# MotherBoard.net
KiCad netlist of a schematic drawn in Altium Designer
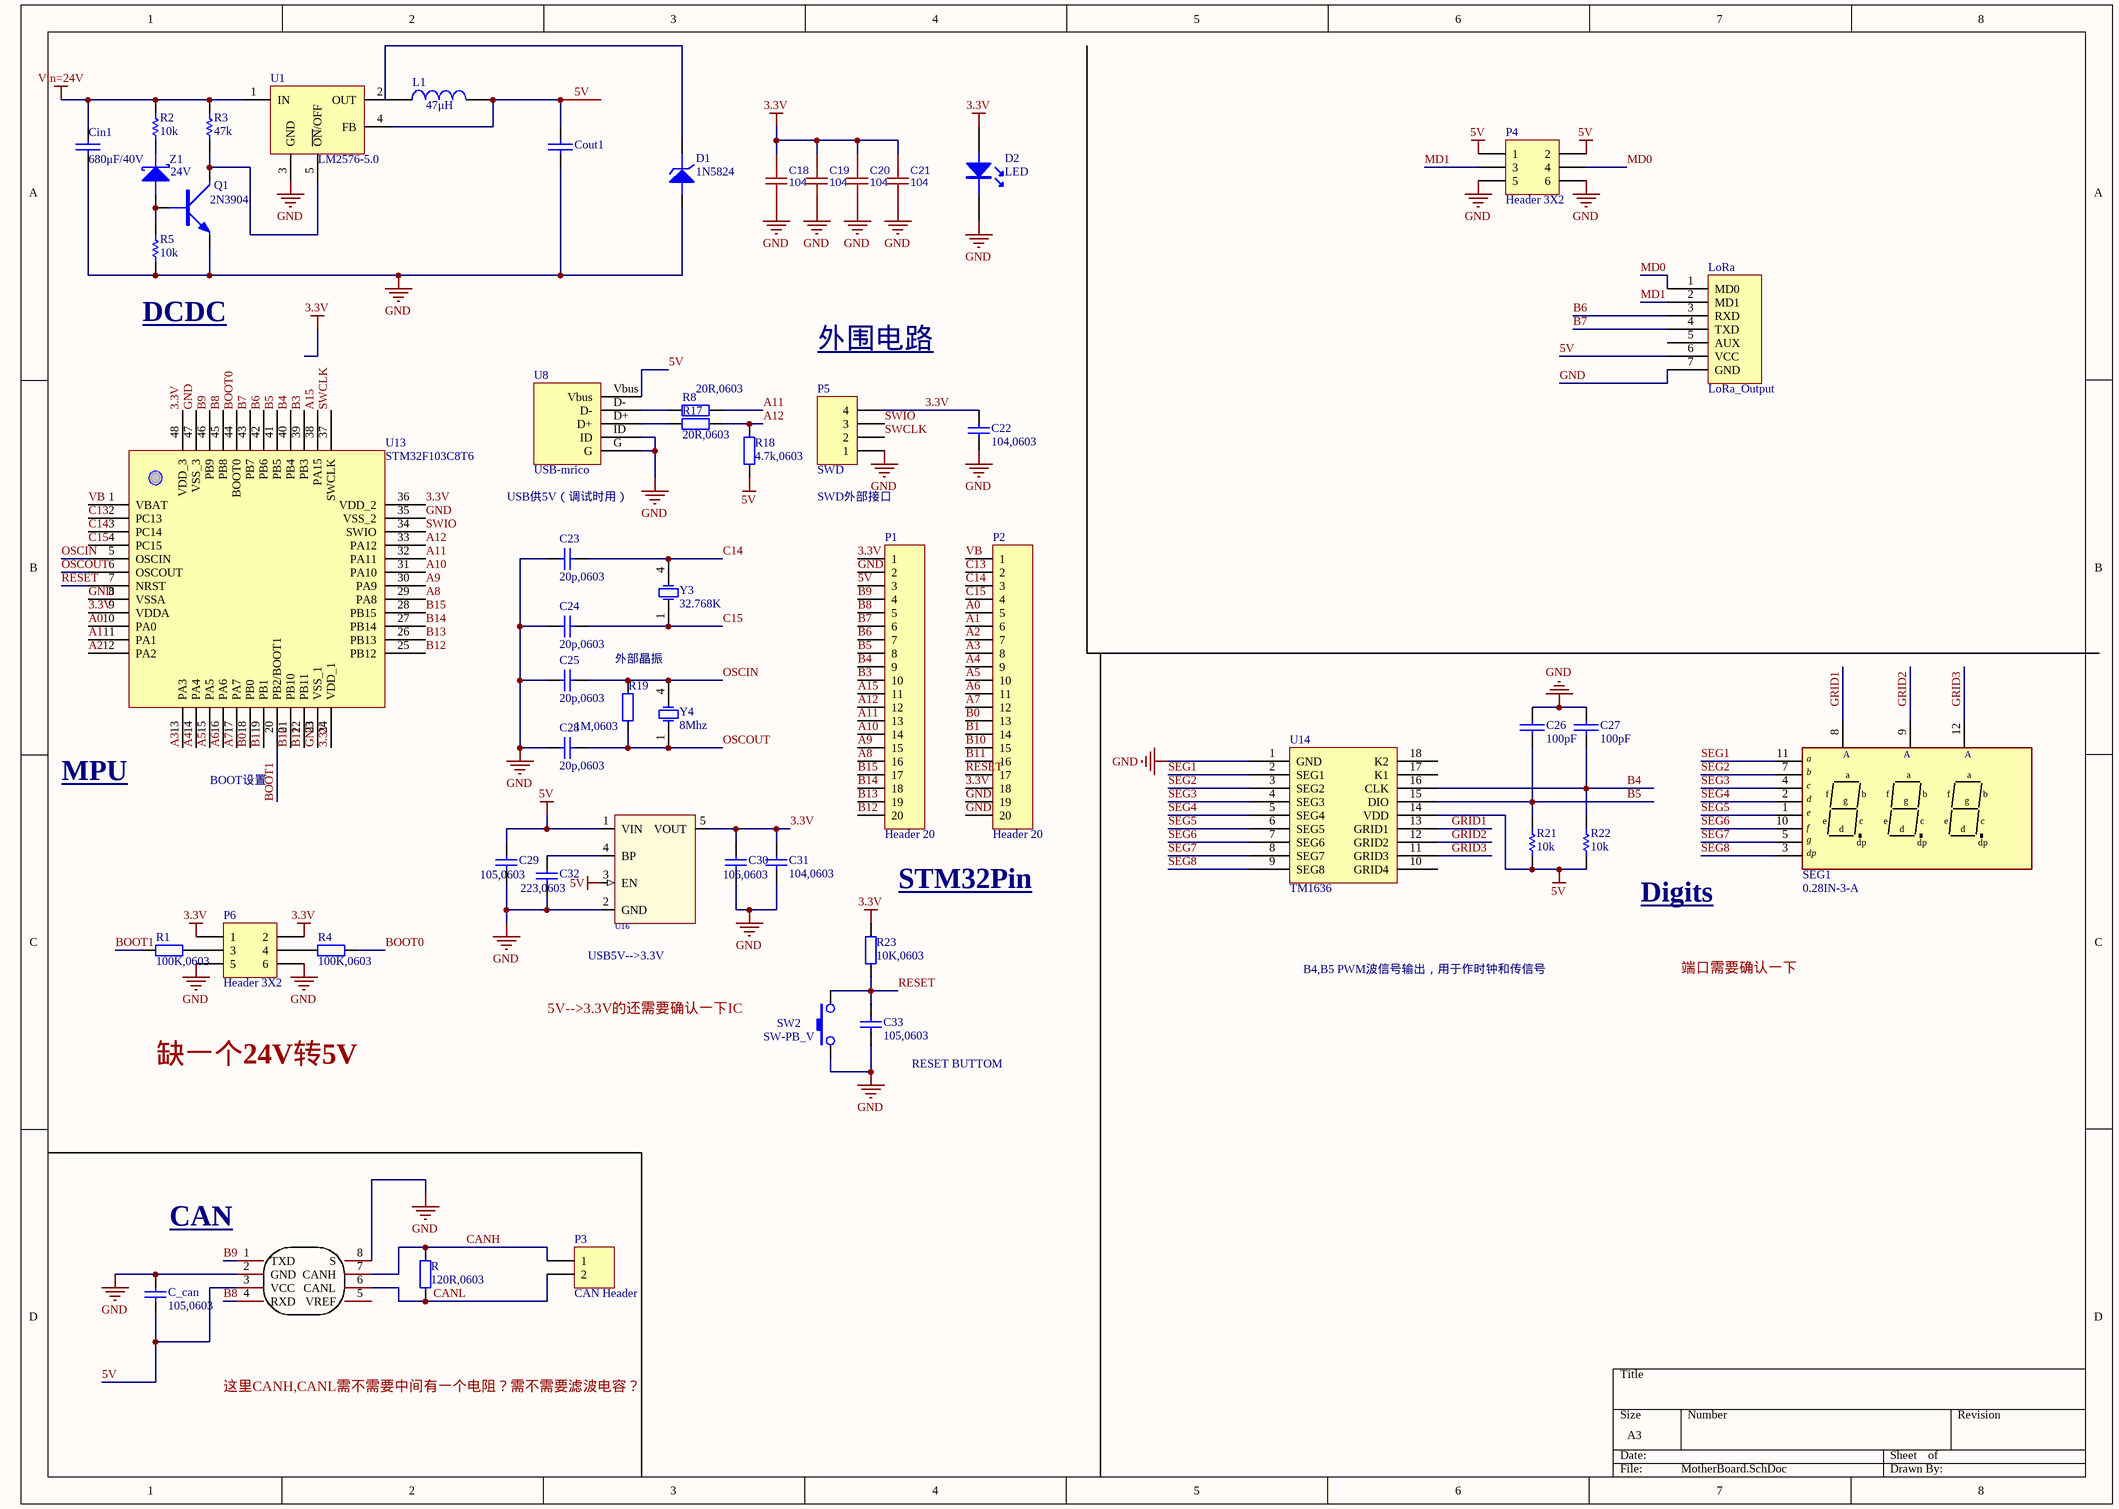
[diagram p0: MotherBoard.SchDoc]

(export (version "E")
  (design (tool "Eeschema 10.0.6"))
  (components
    (comp (ref "C18")
      (value "104")
      (footprint "0805")
      (fields
        (field (name "BOM_MANUFACTURER PART") "0805B103K101NT")
        (field (name "BOM_SUPPLIER PART") "C128805")
        (field (name "CONTRIBUTOR") "LCSC")
      )
      (libsource (lib "LR7843HS") (part "105"))
    )
    (comp (ref "C19")
      (value "104")
      (footprint "0805")
      (fields
        (field (name "BOM_MANUFACTURER PART") "0805B103K101NT")
        (field (name "BOM_SUPPLIER PART") "C128805")
        (field (name "CONTRIBUTOR") "LCSC")
      )
      (libsource (lib "LR7843HS") (part "105"))
    )
    (comp (ref "C20")
      (value "104")
      (footprint "0805")
      (fields
        (field (name "BOM_MANUFACTURER PART") "0805B103K101NT")
        (field (name "BOM_SUPPLIER PART") "C128805")
        (field (name "CONTRIBUTOR") "LCSC")
      )
      (libsource (lib "LR7843HS") (part "105"))
    )
    (comp (ref "C21")
      (value "104")
      (footprint "0805")
      (fields
        (field (name "BOM_MANUFACTURER PART") "0805B103K101NT")
        (field (name "BOM_SUPPLIER PART") "C128805")
        (field (name "CONTRIBUTOR") "LCSC")
      )
      (libsource (lib "LR7843HS") (part "105"))
    )
    (comp (ref "C22")
      (value "104,0603")
      (footprint "C0603")
      (description "Capacitor")
      (fields (field (name "PUBLISHER") "Altium Limited"))
      (libsource (lib "STM32F103C8T6") (part "Cap"))
    )
    (comp (ref "C23")
      (value "20p,0603")
      (footprint "C0603")
      (description "Capacitor")
      (fields (field (name "PUBLISHER") "Altium Limited"))
      (libsource (lib "STM32F103C8T6") (part "Cap"))
    )
    (comp (ref "C24")
      (value "20p,0603")
      (footprint "C0603")
      (description "Capacitor")
      (fields (field (name "PUBLISHER") "Altium Limited"))
      (libsource (lib "STM32F103C8T6") (part "Cap"))
    )
    (comp (ref "C25")
      (value "20p,0603")
      (footprint "C0603")
      (description "Capacitor")
      (fields (field (name "PUBLISHER") "Altium Limited"))
      (libsource (lib "STM32F103C8T6") (part "Cap"))
    )
    (comp (ref "C26")
      (value "100pF")
      (footprint "0201C")
      (description "无极性电容")
      (libsource (lib "电容") (part "CAP"))
    )
    (comp (ref "C27")
      (value "100pF")
      (footprint "0201C")
      (description "无极性电容")
      (libsource (lib "电容") (part "CAP"))
    )
    (comp (ref "C28")
      (value "20p,0603")
      (footprint "C0603")
      (description "Capacitor")
      (fields (field (name "PUBLISHER") "Altium Limited"))
      (libsource (lib "STM32F103C8T6") (part "Cap"))
    )
    (comp (ref "C29")
      (value "105,0603")
      (footprint "C0603")
      (description "Capacitor")
      (fields (field (name "PUBLISHER") "Altium Limited"))
      (libsource (lib "STM32F103C8T6") (part "Cap"))
    )
    (comp (ref "C30")
      (value "106,0603")
      (footprint "C0603")
      (description "Capacitor")
      (fields (field (name "PUBLISHER") "Altium Limited"))
      (libsource (lib "STM32F103C8T6") (part "Cap"))
    )
    (comp (ref "C31")
      (value "104,0603")
      (footprint "C0603")
      (description "Capacitor")
      (fields (field (name "PUBLISHER") "Altium Limited"))
      (libsource (lib "STM32F103C8T6") (part "Cap"))
    )
    (comp (ref "C32")
      (value "223,0603")
      (footprint "C0603")
      (description "Capacitor")
      (fields (field (name "PUBLISHER") "Altium Limited"))
      (libsource (lib "STM32F103C8T6") (part "Cap"))
    )
    (comp (ref "C33")
      (value "105,0603")
      (footprint "C0603")
      (description "Capacitor")
      (fields (field (name "PUBLISHER") "Altium Limited"))
      (libsource (lib "STM32F103C8T6") (part "Cap"))
    )
    (comp (ref "Cin1")
      (value "680μF/40V")
      (footprint "0201C")
      (description "无极性电容")
      (libsource (lib "电容") (part "CAP"))
    )
    (comp (ref "Cout1")
      (value "~")
      (footprint "0201C")
      (description "无极性电容")
      (libsource (lib "电容") (part "CAP"))
    )
    (comp (ref "C_can")
      (value "105,0603")
      (footprint "C0603")
      (description "Capacitor")
      (fields (field (name "PUBLISHER") "Altium Limited"))
      (libsource (lib "STM32F103C8T6") (part "Cap"))
    )
    (comp (ref "D1")
      (value "1N5824")
      (footprint "DO-15")
      (description "稳压二极管")
      (libsource (lib "二极管") (part "DIODE ZENER"))
    )
    (comp (ref "D2") (value "LED") (footprint "LED") (libsource (lib "STM32F103C8T6") (part "LED")))
    (comp (ref "L1")
      (value "47μH")
      (footprint "AL0204")
      (description "INDUCTOR")
      (libsource (lib "电感") (part "INDUCTOR"))
    )
    (comp (ref "LoRa")
      (value "LoRa_Output")
      (footprint "LoRa_Output")
      (libsource (lib "STM32F103C8T6") (part "LoRa_Output"))
    )
    (comp (ref "P1")
      (value "Header 20")
      (footprint "HDR1X20")
      (description "Header, 20-Pin")
      (fields (field (name "PUBLISHER") "Altium Limited"))
      (libsource (lib "STM32F103C8T6") (part "Header 20"))
    )
    (comp (ref "P2")
      (value "Header 20")
      (footprint "HDR1X20")
      (description "Header, 20-Pin")
      (fields (field (name "PUBLISHER") "Altium Limited"))
      (libsource (lib "STM32F103C8T6") (part "Header 20"))
    )
    (comp (ref "P3")
      (value "CAN Header")
      (footprint "HDR1X2")
      (description "Header, 2-Pin")
      (fields (field (name "PUBLISHER") "Altium Limited"))
      (libsource (lib "Miscellaneous Connectors") (part "Header 2"))
    )
    (comp (ref "P4")
      (value "Header 3X2")
      (footprint "HDR2X3")
      (description "Header, 3-Pin, Dual row")
      (fields (field (name "PUBLISHER") "Altium Limited"))
      (libsource (lib "STM32F103C8T6") (part "Header 3X2"))
    )
    (comp (ref "P5")
      (value "SWD")
      (footprint "HDR1X4")
      (description "Header, 4-Pin")
      (fields (field (name "PUBLISHER") "Altium Limited"))
      (libsource (lib "STM32F103C8T6") (part "Header 4"))
    )
    (comp (ref "P6")
      (value "Header 3X2")
      (footprint "HDR2X3")
      (description "Header, 3-Pin, Dual row")
      (fields (field (name "PUBLISHER") "Altium Limited"))
      (libsource (lib "STM32F103C8T6") (part "Header 3X2"))
    )
    (comp (ref "Q1")
      (value "2N3904")
      (footprint "SOT-23")
      (description "NPN三极管")
      (libsource (lib "三极管") (part "NPN"))
    )
    (comp (ref "R")
      (value "120R,0603")
      (footprint "R0603")
      (description "Resistor")
      (fields (field (name "PUBLISHER") "Altium Limited"))
      (libsource (lib "") (part "Res2_1"))
    )
    (comp (ref "R1")
      (value "100K,0603")
      (footprint "R0603")
      (description "Resistor")
      (fields (field (name "PUBLISHER") "Altium Limited"))
      (libsource (lib "STM32F103C8T6") (part "Res2"))
    )
    (comp (ref "R2") (value "10k") (footprint "0201R") (libsource (lib "电阻") (part "RES")))
    (comp (ref "R3") (value "47k") (footprint "0201R") (libsource (lib "电阻") (part "RES")))
    (comp (ref "R4")
      (value "100K,0603")
      (footprint "R0603")
      (description "Resistor")
      (fields (field (name "PUBLISHER") "Altium Limited"))
      (libsource (lib "") (part "Res2_2"))
    )
    (comp (ref "R5") (value "10k") (footprint "0201R") (libsource (lib "电阻") (part "RES")))
    (comp (ref "R8")
      (value "20R,0603")
      (footprint "R0603")
      (description "Resistor")
      (fields (field (name "PUBLISHER") "Altium Limited"))
      (libsource (lib "STM32F103C8T6") (part "Res2"))
    )
    (comp (ref "R17")
      (value "20R,0603")
      (footprint "R0603")
      (description "Resistor")
      (fields (field (name "PUBLISHER") "Altium Limited"))
      (libsource (lib "STM32F103C8T6") (part "Res2"))
    )
    (comp (ref "R18")
      (value "4.7k,0603")
      (footprint "R0603")
      (description "Resistor")
      (fields (field (name "PUBLISHER") "Altium Limited"))
      (libsource (lib "") (part "Res2_1"))
    )
    (comp (ref "R19")
      (value "1M,0603")
      (footprint "R0603")
      (description "Resistor")
      (fields (field (name "PUBLISHER") "Altium Limited"))
      (libsource (lib "") (part "Res2_1"))
    )
    (comp (ref "R21") (value "10k") (footprint "0201R") (libsource (lib "电阻") (part "RES")))
    (comp (ref "R22") (value "10k") (footprint "0201R") (libsource (lib "电阻") (part "RES")))
    (comp (ref "R23")
      (value "10K,0603")
      (footprint "R0603")
      (description "Resistor")
      (fields (field (name "PUBLISHER") "Altium Limited"))
      (libsource (lib "") (part "Res2_1"))
    )
    (comp (ref "SEG1")
      (value "0.28IN-3-A")
      (footprint "0.36IN-3P")
      (description "3位0.28寸共阳数码管")
      (libsource (lib "数码管") (part "0.28IN-3-A"))
    )
    (comp (ref "SW2")
      (value "SW-PB_V")
      (footprint "KEY-SMT")
      (description "SWITCH")
      (libsource (lib "STM32F103C8T6") (part "SW-PB_V"))
    )
    (comp (ref "U1")
      (value "LM2576-5.0")
      (footprint "TO220-5A")
      (description "DC降压芯片")
      (libsource (lib "电源芯片") (part "LM2576-5.0"))
    )
    (comp (ref "U8")
      (value "USB-mrico")
      (footprint "Micro_USB")
      (libsource (lib "STM32F103C8T6") (part "usb-STM"))
    )
    (comp (ref "U13")
      (value "STM32F103C8T6")
      (footprint "48P")
      (libsource (lib "STM32F103C8T6") (part "STM32F103C8T6"))
    )
    (comp (ref "U14")
      (value "TM1636")
      (footprint "74系列芯片:DIP18")
      (description "TM1636LED控制芯片")
      (libsource (lib "74系列芯片") (part "TM1636"))
    )
    (comp (ref "U15")
      (value "TJA1050T/CM,118")
      (footprint "SOIC-8_L5.0-W4.0-P1.27-LS6.0-BL")
      (fields (field (name "MANUFACTURER") "NXP(恩智浦)"))
      (libsource (lib "STM32F103C8T6") (part "TJA1050T/CM,118"))
    )
    (comp (ref "U16")
      (value "RT9193")
      (fields (field (name "ICA_PARTNUM") "$$2191094$$RT9193-15CU5") (field (name "PART NUMBER") "TMP-13"))
      (libsource (lib "STM32F103C8T6") (part "RT9193X_5P"))
    )
    (comp (ref "Y3")
      (value "32.768K")
      (footprint "XTAL1")
      (description "Crystal Oscillator")
      (fields (field (name "PUBLISHER") "Altium Limited"))
      (libsource (lib "STM32F103C8T6") (part "XTAL"))
    )
    (comp (ref "Y4")
      (value "8Mhz")
      (footprint "XTAL1")
      (description "Crystal Oscillator")
      (fields (field (name "PUBLISHER") "Altium Limited"))
      (libsource (lib "STM32F103C8T6") (part "XTAL"))
    )
    (comp (ref "Z1")
      (value "24V")
      (footprint "DO-15")
      (description "肖特基二极管")
      (libsource (lib "二极管") (part "DIODE SCHOTTKY"))
    )
  )
  (nets
    (net (code "1") (name "/A0") (class "Default")
      (node (ref "P2") (pin "5") (pinfunction "5_5") (pintype "passive"))
      (node (ref "U13") (pin "10") (pinfunction "PA0_10") (pintype "passive"))
    )
    (net (code "2") (name "/A1") (class "Default")
      (node (ref "P2") (pin "6") (pinfunction "6_6") (pintype "passive"))
      (node (ref "U13") (pin "11") (pinfunction "PA1_11") (pintype "passive"))
    )
    (net (code "3") (name "/A2") (class "Default")
      (node (ref "P2") (pin "7") (pinfunction "7_7") (pintype "passive"))
      (node (ref "U13") (pin "12") (pinfunction "PA2_12") (pintype "passive"))
    )
    (net (code "4") (name "/A3") (class "Default")
      (node (ref "P2") (pin "8") (pinfunction "8_8") (pintype "passive"))
      (node (ref "U13") (pin "13") (pinfunction "PA3_13") (pintype "passive"))
    )
    (net (code "5") (name "/A4") (class "Default")
      (node (ref "P2") (pin "9") (pinfunction "9_9") (pintype "passive"))
      (node (ref "U13") (pin "14") (pinfunction "PA4_14") (pintype "passive"))
    )
    (net (code "6") (name "/A5") (class "Default")
      (node (ref "P2") (pin "10") (pinfunction "10_10") (pintype "passive"))
      (node (ref "U13") (pin "15") (pinfunction "PA5_15") (pintype "passive"))
    )
    (net (code "7") (name "/A6") (class "Default")
      (node (ref "P2") (pin "11") (pinfunction "11_11") (pintype "passive"))
      (node (ref "U13") (pin "16") (pinfunction "PA6_16") (pintype "passive"))
    )
    (net (code "8") (name "/A7") (class "Default")
      (node (ref "P2") (pin "12") (pinfunction "12_12") (pintype "passive"))
      (node (ref "U13") (pin "17") (pinfunction "PA7_17") (pintype "passive"))
    )
    (net (code "9") (name "/A8") (class "Default")
      (node (ref "P1") (pin "16") (pinfunction "16_16") (pintype "passive"))
      (node (ref "U13") (pin "29") (pinfunction "PA8_29") (pintype "passive"))
    )
    (net (code "10") (name "/A9") (class "Default")
      (node (ref "P1") (pin "15") (pinfunction "15_15") (pintype "passive"))
      (node (ref "U13") (pin "30") (pinfunction "PA9_30") (pintype "passive"))
    )
    (net (code "11") (name "/A10") (class "Default")
      (node (ref "P1") (pin "14") (pinfunction "14_14") (pintype "passive"))
      (node (ref "U13") (pin "31") (pinfunction "PA10_31") (pintype "passive"))
    )
    (net (code "12") (name "/A11") (class "Default")
      (node (ref "P1") (pin "13") (pinfunction "13_13") (pintype "passive"))
      (node (ref "R8") (pin "2") (pinfunction "2_2") (pintype "passive"))
      (node (ref "U13") (pin "32") (pinfunction "PA11_32") (pintype "passive"))
    )
    (net (code "13") (name "/A12") (class "Default")
      (node (ref "P1") (pin "12") (pinfunction "12_12") (pintype "passive"))
      (node (ref "R17") (pin "2") (pinfunction "2_2") (pintype "passive"))
      (node (ref "R18") (pin "2") (pinfunction "2_2") (pintype "passive"))
      (node (ref "U13") (pin "33") (pinfunction "PA12_33") (pintype "passive"))
    )
    (net (code "14") (name "/A15") (class "Default")
      (node (ref "P1") (pin "11") (pinfunction "11_11") (pintype "passive"))
      (node (ref "U13") (pin "38") (pinfunction "PA15_38") (pintype "passive"))
    )
    (net (code "15") (name "/B0") (class "Default")
      (node (ref "P2") (pin "13") (pinfunction "13_13") (pintype "passive"))
      (node (ref "U13") (pin "18") (pinfunction "PB0_18") (pintype "passive"))
    )
    (net (code "16") (name "/B1") (class "Default")
      (node (ref "P2") (pin "14") (pinfunction "14_14") (pintype "passive"))
      (node (ref "U13") (pin "19") (pinfunction "PB1_19") (pintype "passive"))
    )
    (net (code "17") (name "/B3") (class "Default")
      (node (ref "P1") (pin "10") (pinfunction "10_10") (pintype "passive"))
      (node (ref "U13") (pin "39") (pinfunction "PB3_39") (pintype "passive"))
    )
    (net (code "18") (name "/B4") (class "Default")
      (node (ref "C27") (pin "1") (pinfunction "1_1") (pintype "passive"))
      (node (ref "P1") (pin "9") (pinfunction "9_9") (pintype "passive"))
      (node (ref "R22") (pin "2") (pinfunction "2_2") (pintype "passive"))
      (node (ref "U13") (pin "40") (pinfunction "PB4_40") (pintype "passive"))
      (node (ref "U14") (pin "16") (pinfunction "CLK_16") (pintype "passive"))
    )
    (net (code "19") (name "/B5") (class "Default")
      (node (ref "C26") (pin "1") (pinfunction "1_1") (pintype "passive"))
      (node (ref "P1") (pin "8") (pinfunction "8_8") (pintype "passive"))
      (node (ref "R21") (pin "2") (pinfunction "2_2") (pintype "passive"))
      (node (ref "U13") (pin "41") (pinfunction "PB5_41") (pintype "passive"))
      (node (ref "U14") (pin "15") (pinfunction "DIO_15") (pintype "passive"))
    )
    (net (code "20") (name "/B6") (class "Default")
      (node (ref "LoRa") (pin "3") (pinfunction "RXD_3") (pintype "passive"))
      (node (ref "P1") (pin "7") (pinfunction "7_7") (pintype "passive"))
      (node (ref "U13") (pin "42") (pinfunction "PB6_42") (pintype "passive"))
    )
    (net (code "21") (name "/B7") (class "Default")
      (node (ref "LoRa") (pin "4") (pinfunction "TXD_4") (pintype "passive"))
      (node (ref "P1") (pin "6") (pinfunction "6_6") (pintype "passive"))
      (node (ref "U13") (pin "43") (pinfunction "PB7_43") (pintype "passive"))
    )
    (net (code "22") (name "/B8") (class "Default")
      (node (ref "P1") (pin "5") (pinfunction "5_5") (pintype "passive"))
      (node (ref "U13") (pin "45") (pinfunction "PB8_45") (pintype "passive"))
      (node (ref "U15") (pin "4") (pinfunction "RXD_4") (pintype "passive"))
    )
    (net (code "23") (name "/B9") (class "Default")
      (node (ref "P1") (pin "4") (pinfunction "4_4") (pintype "passive"))
      (node (ref "U13") (pin "46") (pinfunction "PB9_46") (pintype "passive"))
      (node (ref "U15") (pin "1") (pinfunction "TXD_1") (pintype "passive"))
    )
    (net (code "24") (name "/B10") (class "Default")
      (node (ref "P2") (pin "15") (pinfunction "15_15") (pintype "passive"))
      (node (ref "U13") (pin "21") (pinfunction "PB10_21") (pintype "passive"))
    )
    (net (code "25") (name "/B11") (class "Default")
      (node (ref "P2") (pin "16") (pinfunction "16_16") (pintype "passive"))
      (node (ref "U13") (pin "22") (pinfunction "PB11_22") (pintype "passive"))
    )
    (net (code "26") (name "/B12") (class "Default")
      (node (ref "P1") (pin "20") (pinfunction "20_20") (pintype "passive"))
      (node (ref "U13") (pin "25") (pinfunction "PB12_25") (pintype "passive"))
    )
    (net (code "27") (name "/B13") (class "Default")
      (node (ref "P1") (pin "19") (pinfunction "19_19") (pintype "passive"))
      (node (ref "U13") (pin "26") (pinfunction "PB13_26") (pintype "passive"))
    )
    (net (code "28") (name "/B14") (class "Default")
      (node (ref "P1") (pin "18") (pinfunction "18_18") (pintype "passive"))
      (node (ref "U13") (pin "27") (pinfunction "PB14_27") (pintype "passive"))
    )
    (net (code "29") (name "/B15") (class "Default")
      (node (ref "P1") (pin "17") (pinfunction "17_17") (pintype "passive"))
      (node (ref "U13") (pin "28") (pinfunction "PB15_28") (pintype "passive"))
    )
    (net (code "30") (name "/BOOT0") (class "Default")
      (node (ref "R4") (pin "1") (pinfunction "1_1") (pintype "passive"))
      (node (ref "U13") (pin "44") (pinfunction "BOOT0_44") (pintype "passive"))
    )
    (net (code "31") (name "/BOOT1") (class "Default")
      (node (ref "R1") (pin "1") (pinfunction "1_1") (pintype "passive"))
      (node (ref "U13") (pin "20") (pinfunction "PB2/BOOT1_20") (pintype "passive"))
    )
    (net (code "32") (name "/C13") (class "Default")
      (node (ref "P2") (pin "2") (pinfunction "2_2") (pintype "passive"))
      (node (ref "U13") (pin "2") (pinfunction "PC13_2") (pintype "passive"))
    )
    (net (code "33") (name "/C14") (class "Default")
      (node (ref "C23") (pin "2") (pinfunction "2_2") (pintype "passive"))
      (node (ref "P2") (pin "3") (pinfunction "3_3") (pintype "passive"))
      (node (ref "U13") (pin "3") (pinfunction "PC14_3") (pintype "passive"))
      (node (ref "Y3") (pin "4") (pinfunction "OSC2_4") (pintype "passive"))
    )
    (net (code "34") (name "/C15") (class "Default")
      (node (ref "C24") (pin "2") (pinfunction "2_2") (pintype "passive"))
      (node (ref "P2") (pin "4") (pinfunction "4_4") (pintype "passive"))
      (node (ref "U13") (pin "4") (pinfunction "PC15_4") (pintype "passive"))
      (node (ref "Y3") (pin "1") (pinfunction "OSC1_1") (pintype "passive"))
    )
    (net (code "35") (name "/CANH") (class "Default")
      (node (ref "P3") (pin "1") (pinfunction "1_1") (pintype "passive"))
      (node (ref "R") (pin "2") (pinfunction "2_2") (pintype "passive"))
      (node (ref "U15") (pin "7") (pinfunction "CANH_7") (pintype "passive"))
    )
    (net (code "36") (name "/CANL") (class "Default")
      (node (ref "P3") (pin "2") (pinfunction "2_2") (pintype "passive"))
      (node (ref "R") (pin "1") (pinfunction "1_1") (pintype "passive"))
      (node (ref "U15") (pin "6") (pinfunction "CANL_6") (pintype "passive"))
    )
    (net (code "37") (name "/GRID1") (class "Default")
      (node (ref "SEG1") (pin "8") (pinfunction "8_8") (pintype "passive"))
      (node (ref "U14") (pin "13") (pinfunction "GRID1_13") (pintype "passive"))
    )
    (net (code "38") (name "/GRID2") (class "Default")
      (node (ref "SEG1") (pin "9") (pinfunction "9_9") (pintype "passive"))
      (node (ref "U14") (pin "12") (pinfunction "GRID2_12") (pintype "passive"))
    )
    (net (code "39") (name "/GRID3") (class "Default")
      (node (ref "SEG1") (pin "12") (pinfunction "12_12") (pintype "passive"))
      (node (ref "U14") (pin "11") (pinfunction "GRID3_11") (pintype "passive"))
    )
    (net (code "40") (name "/MD0") (class "Default")
      (node (ref "LoRa") (pin "1") (pinfunction "MD0_1") (pintype "passive"))
      (node (ref "P4") (pin "4") (pinfunction "4_4") (pintype "passive"))
    )
    (net (code "41") (name "/MD1") (class "Default")
      (node (ref "LoRa") (pin "2") (pinfunction "MD1_2") (pintype "passive"))
      (node (ref "P4") (pin "3") (pinfunction "3_3") (pintype "passive"))
    )
    (net (code "42") (name "/OSCIN") (class "Default")
      (node (ref "C25") (pin "2") (pinfunction "2_2") (pintype "passive"))
      (node (ref "R19") (pin "2") (pinfunction "2_2") (pintype "passive"))
      (node (ref "U13") (pin "5") (pinfunction "OSCIN_5") (pintype "passive"))
      (node (ref "Y4") (pin "4") (pinfunction "OSC2_4") (pintype "passive"))
    )
    (net (code "43") (name "/OSCOUT") (class "Default")
      (node (ref "C28") (pin "2") (pinfunction "2_2") (pintype "passive"))
      (node (ref "R19") (pin "1") (pinfunction "1_1") (pintype "passive"))
      (node (ref "U13") (pin "6") (pinfunction "OSCOUT_6") (pintype "passive"))
      (node (ref "Y4") (pin "1") (pinfunction "OSC1_1") (pintype "passive"))
    )
    (net (code "44") (name "/RESET") (class "Default")
      (node (ref "C33") (pin "2") (pinfunction "2_2") (pintype "passive"))
      (node (ref "P2") (pin "17") (pinfunction "17_17") (pintype "passive"))
      (node (ref "R23") (pin "1") (pinfunction "1_1") (pintype "passive"))
      (node (ref "SW2") (pin "2") (pinfunction "2_2") (pintype "passive"))
      (node (ref "U13") (pin "7") (pinfunction "NRST_7") (pintype "passive"))
    )
    (net (code "45") (name "/SEG1") (class "Default")
      (node (ref "SEG1") (pin "11") (pinfunction "11_11") (pintype "passive"))
      (node (ref "U14") (pin "2") (pinfunction "SEG1_2") (pintype "passive"))
    )
    (net (code "46") (name "/SEG2") (class "Default")
      (node (ref "SEG1") (pin "7") (pinfunction "7_7") (pintype "passive"))
      (node (ref "U14") (pin "3") (pinfunction "SEG2_3") (pintype "passive"))
    )
    (net (code "47") (name "/SEG3") (class "Default")
      (node (ref "SEG1") (pin "4") (pinfunction "4_4") (pintype "passive"))
      (node (ref "U14") (pin "4") (pinfunction "SEG3_4") (pintype "passive"))
    )
    (net (code "48") (name "/SEG4") (class "Default")
      (node (ref "SEG1") (pin "2") (pinfunction "2_2") (pintype "passive"))
      (node (ref "U14") (pin "5") (pinfunction "SEG4_5") (pintype "passive"))
    )
    (net (code "49") (name "/SEG5") (class "Default")
      (node (ref "SEG1") (pin "1") (pinfunction "1_1") (pintype "passive"))
      (node (ref "U14") (pin "6") (pinfunction "SEG5_6") (pintype "passive"))
    )
    (net (code "50") (name "/SEG6") (class "Default")
      (node (ref "SEG1") (pin "10") (pinfunction "10_10") (pintype "passive"))
      (node (ref "U14") (pin "7") (pinfunction "SEG6_7") (pintype "passive"))
    )
    (net (code "51") (name "/SEG7") (class "Default")
      (node (ref "SEG1") (pin "5") (pinfunction "5_5") (pintype "passive"))
      (node (ref "U14") (pin "8") (pinfunction "SEG7_8") (pintype "passive"))
    )
    (net (code "52") (name "/SEG8") (class "Default")
      (node (ref "SEG1") (pin "3") (pinfunction "3_3") (pintype "passive"))
      (node (ref "U14") (pin "9") (pinfunction "SEG8_9") (pintype "passive"))
    )
    (net (code "53") (name "/SWCLK") (class "Default")
      (node (ref "P5") (pin "2") (pinfunction "2_2") (pintype "passive"))
      (node (ref "U13") (pin "37") (pinfunction "SWCLK_37") (pintype "passive"))
    )
    (net (code "54") (name "/SWIO") (class "Default")
      (node (ref "P5") (pin "3") (pinfunction "3_3") (pintype "passive"))
      (node (ref "U13") (pin "34") (pinfunction "SWIO_34") (pintype "passive"))
    )
    (net (code "55") (name "/VB") (class "Default")
      (node (ref "P2") (pin "1") (pinfunction "1_1") (pintype "passive"))
      (node (ref "U13") (pin "1") (pinfunction "VBAT_1") (pintype "passive"))
    )
    (net (code "56") (name "3.3V") (class "Default")
      (node (ref "C18") (pin "2") (pinfunction "2_2") (pintype "passive"))
      (node (ref "C19") (pin "2") (pinfunction "2_2") (pintype "passive"))
      (node (ref "C20") (pin "2") (pinfunction "2_2") (pintype "passive"))
      (node (ref "C21") (pin "2") (pinfunction "2_2") (pintype "passive"))
      (node (ref "C22") (pin "2") (pinfunction "2_2") (pintype "passive"))
      (node (ref "C30") (pin "1") (pinfunction "1_1") (pintype "passive"))
      (node (ref "C31") (pin "1") (pinfunction "1_1") (pintype "passive"))
      (node (ref "D2") (pin "A") (pinfunction "1_A") (pintype "passive"))
      (node (ref "P1") (pin "1") (pinfunction "1_1") (pintype "passive"))
      (node (ref "P2") (pin "18") (pinfunction "18_18") (pintype "passive"))
      (node (ref "P5") (pin "4") (pinfunction "4_4") (pintype "passive"))
      (node (ref "P6") (pin "1") (pinfunction "1_1") (pintype "passive"))
      (node (ref "P6") (pin "2") (pinfunction "2_2") (pintype "passive"))
      (node (ref "R23") (pin "2") (pinfunction "2_2") (pintype "passive"))
      (node (ref "U13") (pin "24") (pinfunction "VDD_1_24") (pintype "passive"))
      (node (ref "U13") (pin "36") (pinfunction "VDD_2_36") (pintype "passive"))
      (node (ref "U13") (pin "48") (pinfunction "VDD_3_48") (pintype "passive"))
      (node (ref "U13") (pin "9") (pinfunction "VDDA_9") (pintype "passive"))
      (node (ref "U16") (pin "5") (pinfunction "VOUT_5") (pintype "power_in"))
    )
    (net (code "57") (name "5V") (class "Default")
      (node (ref "C29") (pin "1") (pinfunction "1_1") (pintype "passive"))
      (node (ref "C_can") (pin "1") (pinfunction "1_1") (pintype "passive"))
      (node (ref "Cout1") (pin "1") (pinfunction "1_1") (pintype "passive"))
      (node (ref "L1") (pin "2") (pinfunction "2_2") (pintype "passive"))
      (node (ref "LoRa") (pin "6") (pinfunction "VCC_6") (pintype "passive"))
      (node (ref "P1") (pin "3") (pinfunction "3_3") (pintype "passive"))
      (node (ref "P4") (pin "1") (pinfunction "1_1") (pintype "passive"))
      (node (ref "P4") (pin "2") (pinfunction "2_2") (pintype "passive"))
      (node (ref "R18") (pin "1") (pinfunction "1_1") (pintype "passive"))
      (node (ref "R21") (pin "1") (pinfunction "1_1") (pintype "passive"))
      (node (ref "R22") (pin "1") (pinfunction "1_1") (pintype "passive"))
      (node (ref "U1") (pin "4") (pinfunction "FB_4") (pintype "passive"))
      (node (ref "U14") (pin "14") (pinfunction "VDD_14") (pintype "passive"))
      (node (ref "U15") (pin "3") (pinfunction "VCC_3") (pintype "passive"))
      (node (ref "U16") (pin "1") (pinfunction "VIN_1") (pintype "power_in"))
      (node (ref "U16") (pin "3") (pinfunction "EN_3") (pintype "input"))
      (node (ref "U8") (pin "Vbus") (pinfunction "Vbus_Vbus") (pintype "passive"))
    )
    (net (code "58") (name "GND") (class "Default")
      (node (ref "C18") (pin "1") (pinfunction "1_1") (pintype "passive"))
      (node (ref "C19") (pin "1") (pinfunction "1_1") (pintype "passive"))
      (node (ref "C20") (pin "1") (pinfunction "1_1") (pintype "passive"))
      (node (ref "C21") (pin "1") (pinfunction "1_1") (pintype "passive"))
      (node (ref "C22") (pin "1") (pinfunction "1_1") (pintype "passive"))
      (node (ref "C23") (pin "1") (pinfunction "1_1") (pintype "passive"))
      (node (ref "C24") (pin "1") (pinfunction "1_1") (pintype "passive"))
      (node (ref "C25") (pin "1") (pinfunction "1_1") (pintype "passive"))
      (node (ref "C26") (pin "2") (pinfunction "2_2") (pintype "passive"))
      (node (ref "C27") (pin "2") (pinfunction "2_2") (pintype "passive"))
      (node (ref "C28") (pin "1") (pinfunction "1_1") (pintype "passive"))
      (node (ref "C29") (pin "2") (pinfunction "2_2") (pintype "passive"))
      (node (ref "C30") (pin "2") (pinfunction "2_2") (pintype "passive"))
      (node (ref "C31") (pin "2") (pinfunction "2_2") (pintype "passive"))
      (node (ref "C32") (pin "2") (pinfunction "2_2") (pintype "passive"))
      (node (ref "C33") (pin "1") (pinfunction "1_1") (pintype "passive"))
      (node (ref "C_can") (pin "2") (pinfunction "2_2") (pintype "passive"))
      (node (ref "Cin1") (pin "1") (pinfunction "1_1") (pintype "passive"))
      (node (ref "Cout1") (pin "2") (pinfunction "2_2") (pintype "passive"))
      (node (ref "D1") (pin "A") (pinfunction "A_A") (pintype "passive"))
      (node (ref "D2") (pin "K") (pinfunction "2_K") (pintype "passive"))
      (node (ref "LoRa") (pin "7") (pinfunction "GND_7") (pintype "passive"))
      (node (ref "P1") (pin "2") (pinfunction "2_2") (pintype "passive"))
      (node (ref "P2") (pin "19") (pinfunction "19_19") (pintype "passive"))
      (node (ref "P2") (pin "20") (pinfunction "20_20") (pintype "passive"))
      (node (ref "P4") (pin "5") (pinfunction "5_5") (pintype "passive"))
      (node (ref "P4") (pin "6") (pinfunction "6_6") (pintype "passive"))
      (node (ref "P5") (pin "1") (pinfunction "1_1") (pintype "passive"))
      (node (ref "P6") (pin "5") (pinfunction "5_5") (pintype "passive"))
      (node (ref "P6") (pin "6") (pinfunction "6_6") (pintype "passive"))
      (node (ref "Q1") (pin "E") (pinfunction "E_E") (pintype "passive"))
      (node (ref "R5") (pin "1") (pinfunction "1_1") (pintype "passive"))
      (node (ref "SW2") (pin "1") (pinfunction "1_1") (pintype "passive"))
      (node (ref "U1") (pin "3") (pinfunction "GND_3") (pintype "power_in"))
      (node (ref "U13") (pin "23") (pinfunction "VSS_1_23") (pintype "passive"))
      (node (ref "U13") (pin "35") (pinfunction "VSS_2_35") (pintype "passive"))
      (node (ref "U13") (pin "47") (pinfunction "VSS_3_47") (pintype "passive"))
      (node (ref "U13") (pin "8") (pinfunction "VSSA_8") (pintype "passive"))
      (node (ref "U14") (pin "1") (pinfunction "GND_1") (pintype "passive"))
      (node (ref "U15") (pin "2") (pinfunction "GND_2") (pintype "passive"))
      (node (ref "U15") (pin "8") (pinfunction "S_8") (pintype "passive"))
      (node (ref "U16") (pin "2") (pinfunction "GND_2") (pintype "power_in"))
      (node (ref "U8") (pin "G") (pinfunction "G_G") (pintype "passive"))
      (node (ref "U8") (pin "ID") (pinfunction "ID_ID") (pintype "passive"))
    )
    (net (code "59") (name "Net-(D1-PadK)") (class "Default")
      (node (ref "D1") (pin "K") (pinfunction "K_K") (pintype "passive"))
      (node (ref "L1") (pin "1") (pinfunction "1_1") (pintype "passive"))
    )
    (net (code "60") (name "Net-(P6-Pad3)") (class "Default")
      (node (ref "P6") (pin "3") (pinfunction "3_3") (pintype "passive"))
      (node (ref "R1") (pin "2") (pinfunction "2_2") (pintype "passive"))
    )
    (net (code "61") (name "Net-(P6-Pad4)") (class "Default")
      (node (ref "P6") (pin "4") (pinfunction "4_4") (pintype "passive"))
      (node (ref "R4") (pin "2") (pinfunction "2_2") (pintype "passive"))
    )
    (net (code "62") (name "Net-(Q1-PadB)") (class "Default")
      (node (ref "Q1") (pin "B") (pinfunction "B_B") (pintype "passive"))
      (node (ref "R5") (pin "2") (pinfunction "2_2") (pintype "passive"))
      (node (ref "Z1") (pin "A") (pinfunction "A_A") (pintype "passive"))
    )
    (net (code "63") (name "Net-(R2-Pad1)") (class "Default")
      (node (ref "R2") (pin "1") (pinfunction "1_1") (pintype "passive"))
      (node (ref "Z1") (pin "K") (pinfunction "K_K") (pintype "passive"))
    )
    (net (code "64") (name "Net-(R8-Pad1)") (class "Default")
      (node (ref "R8") (pin "1") (pinfunction "1_1") (pintype "passive"))
      (node (ref "U8") (pin "D-") (pinfunction "D-_D-") (pintype "passive"))
    )
    (net (code "65") (name "Net-(R17-Pad1)") (class "Default")
      (node (ref "R17") (pin "1") (pinfunction "1_1") (pintype "passive"))
      (node (ref "U8") (pin "D+") (pinfunction "D+_D+") (pintype "passive"))
    )
    (net (code "66") (name "Net-(U1-~{ON}{slash}OFF)") (class "Default")
      (node (ref "Q1") (pin "C") (pinfunction "C_C") (pintype "passive"))
      (node (ref "R3") (pin "1") (pinfunction "1_1") (pintype "passive"))
      (node (ref "U1") (pin "5") (pinfunction "~{ON}/OFF_5") (pintype "passive"))
    )
    (net (code "67") (name "Net-(U16-BP)") (class "Default")
      (node (ref "C32") (pin "1") (pinfunction "1_1") (pintype "passive"))
      (node (ref "U16") (pin "4") (pinfunction "BP_4") (pintype "passive"))
    )
    (net (code "68") (name "Vin=24V") (class "Default")
      (node (ref "Cin1") (pin "2") (pinfunction "2_2") (pintype "passive"))
      (node (ref "R2") (pin "2") (pinfunction "2_2") (pintype "passive"))
      (node (ref "R3") (pin "2") (pinfunction "2_2") (pintype "passive"))
      (node (ref "U1") (pin "1") (pinfunction "IN_1") (pintype "power_in"))
    )
    (net (code "69") (name "unconnected-(LoRa-AUX-Pad5)") (class "Default")
      (node (ref "LoRa") (pin "5") (pinfunction "AUX_5") (pintype "passive"))
    )
    (net (code "70") (name "unconnected-(U1-OUT-Pad2)") (class "Default")
      (node (ref "U1") (pin "2") (pinfunction "OUT_2") (pintype "power_in"))
    )
    (net (code "71") (name "unconnected-(U14-GRID4-Pad10)") (class "Default")
      (node (ref "U14") (pin "10") (pinfunction "GRID4_10") (pintype "passive"))
    )
    (net (code "72") (name "unconnected-(U14-K1-Pad17)") (class "Default")
      (node (ref "U14") (pin "17") (pinfunction "K1_17") (pintype "passive"))
    )
    (net (code "73") (name "unconnected-(U14-K2-Pad18)") (class "Default")
      (node (ref "U14") (pin "18") (pinfunction "K2_18") (pintype "passive"))
    )
    (net (code "74") (name "unconnected-(U15-VREF-Pad5)") (class "Default")
      (node (ref "U15") (pin "5") (pinfunction "VREF_5") (pintype "passive"))
    )
  )
)
